# hall_effect_breakout_2025-11-21.net
KiCad netlist of a schematic drawn in EasyEDA Pro
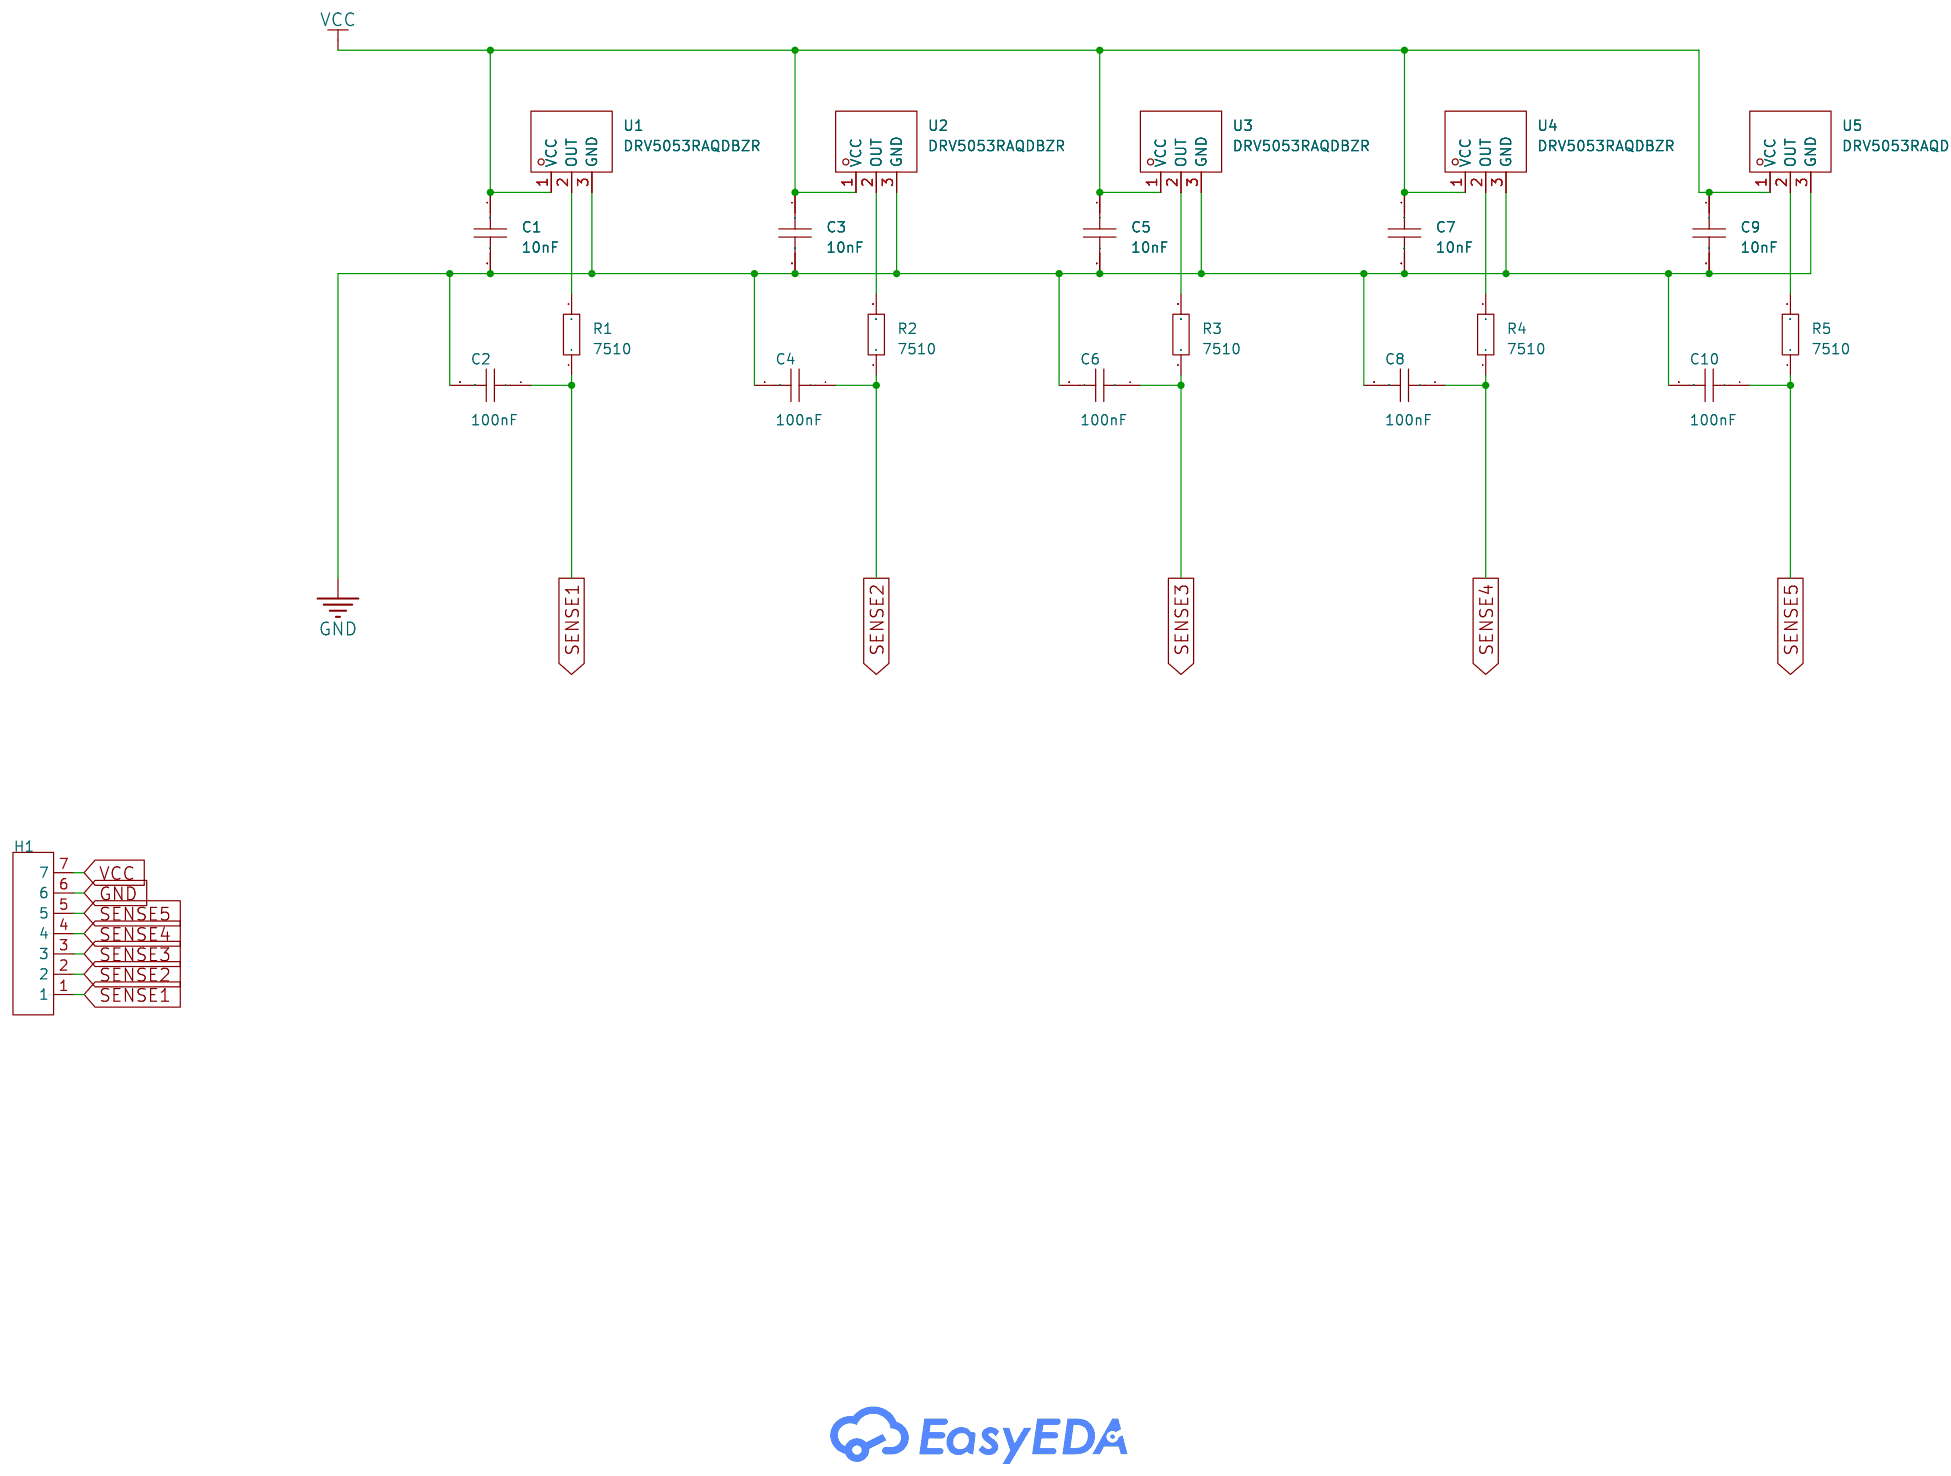
[diagram p0: schematic sheet]

(export (version "E")
  (design (tool "Eeschema 10.0.6"))
  (components
    (comp (ref "C1")
      (value "10nF")
      (footprint "easyedapro:C0603")
      (libsource (lib "easyedapro") (part "CAP"))
    )
    (comp (ref "C2")
      (value "100nF")
      (footprint "easyedapro:C0603")
      (libsource (lib "easyedapro") (part "CAP"))
    )
    (comp (ref "C3")
      (value "10nF")
      (footprint "easyedapro:C0603")
      (libsource (lib "easyedapro") (part "CAP"))
    )
    (comp (ref "C4")
      (value "100nF")
      (footprint "easyedapro:C0603")
      (libsource (lib "easyedapro") (part "CAP"))
    )
    (comp (ref "C5")
      (value "10nF")
      (footprint "easyedapro:C0603")
      (libsource (lib "easyedapro") (part "CAP"))
    )
    (comp (ref "C6")
      (value "100nF")
      (footprint "easyedapro:C0603")
      (libsource (lib "easyedapro") (part "CAP"))
    )
    (comp (ref "C7")
      (value "10nF")
      (footprint "easyedapro:C0603")
      (libsource (lib "easyedapro") (part "CAP"))
    )
    (comp (ref "C8")
      (value "100nF")
      (footprint "easyedapro:C0603")
      (libsource (lib "easyedapro") (part "CAP"))
    )
    (comp (ref "C9")
      (value "10nF")
      (footprint "easyedapro:C0603")
      (libsource (lib "easyedapro") (part "CAP"))
    )
    (comp (ref "C10")
      (value "100nF")
      (footprint "easyedapro:C0603")
      (libsource (lib "easyedapro") (part "CAP"))
    )
    (comp (ref "H1")
      (value "PZ254V-11-07P")
      (footprint "easyedapro:HDR-TH_7P-P2.54-V-M")
      (fields (field (name "Manufacturer") "XFCN(兴飞)"))
      (libsource (lib "easyedapro") (part "PZ254V-11-07P"))
    )
    (comp (ref "R1")
      (value "7510")
      (footprint "easyedapro:R0603")
      (libsource (lib "easyedapro") (part "Res"))
    )
    (comp (ref "R2")
      (value "7510")
      (footprint "easyedapro:R0603")
      (libsource (lib "easyedapro") (part "Res"))
    )
    (comp (ref "R3")
      (value "7510")
      (footprint "easyedapro:R0603")
      (libsource (lib "easyedapro") (part "Res"))
    )
    (comp (ref "R4")
      (value "7510")
      (footprint "easyedapro:R0603")
      (libsource (lib "easyedapro") (part "Res"))
    )
    (comp (ref "R5")
      (value "7510")
      (footprint "easyedapro:R0603")
      (libsource (lib "easyedapro") (part "Res"))
    )
    (comp (ref "U1")
      (value "DRV5053RAQDBZR")
      (footprint "easyedapro:SOT-23-3_L2.9-W1.3-P1.90-LS2.4-BR")
      (fields (field (name "Manufacturer") "TI(德州仪器)"))
      (libsource (lib "easyedapro") (part "DRV5053EAQDBZTQ1"))
    )
    (comp (ref "U2")
      (value "DRV5053RAQDBZR")
      (footprint "easyedapro:SOT-23-3_L2.9-W1.3-P1.90-LS2.4-BR")
      (fields (field (name "Manufacturer") "TI(德州仪器)"))
      (libsource (lib "easyedapro") (part "DRV5053EAQDBZTQ1"))
    )
    (comp (ref "U3")
      (value "DRV5053RAQDBZR")
      (footprint "easyedapro:SOT-23-3_L2.9-W1.3-P1.90-LS2.4-BR")
      (fields (field (name "Manufacturer") "TI(德州仪器)"))
      (libsource (lib "easyedapro") (part "DRV5053EAQDBZTQ1"))
    )
    (comp (ref "U4")
      (value "DRV5053RAQDBZR")
      (footprint "easyedapro:SOT-23-3_L2.9-W1.3-P1.90-LS2.4-BR")
      (fields (field (name "Manufacturer") "TI(德州仪器)"))
      (libsource (lib "easyedapro") (part "DRV5053EAQDBZTQ1"))
    )
    (comp (ref "U5")
      (value "DRV5053RAQDBZR")
      (footprint "easyedapro:SOT-23-3_L2.9-W1.3-P1.90-LS2.4-BR")
      (fields (field (name "Manufacturer") "TI(德州仪器)"))
      (libsource (lib "easyedapro") (part "DRV5053EAQDBZTQ1"))
    )
  )
  (nets
    (net (code "1") (name "GND") (class "Default")
      (node (ref "C1") (pin "2") (pinfunction "2_2") (pintype "input"))
      (node (ref "C10") (pin "2") (pinfunction "2_2") (pintype "input"))
      (node (ref "C2") (pin "2") (pinfunction "2_2") (pintype "input"))
      (node (ref "C3") (pin "2") (pinfunction "2_2") (pintype "input"))
      (node (ref "C4") (pin "2") (pinfunction "2_2") (pintype "input"))
      (node (ref "C5") (pin "2") (pinfunction "2_2") (pintype "input"))
      (node (ref "C6") (pin "2") (pinfunction "2_2") (pintype "input"))
      (node (ref "C7") (pin "2") (pinfunction "2_2") (pintype "input"))
      (node (ref "C8") (pin "2") (pinfunction "2_2") (pintype "input"))
      (node (ref "C9") (pin "2") (pinfunction "2_2") (pintype "input"))
      (node (ref "H1") (pin "6") (pinfunction "6_6") (pintype "unspecified"))
      (node (ref "U1") (pin "3") (pinfunction "GND_3") (pintype "unspecified"))
      (node (ref "U2") (pin "3") (pinfunction "GND_3") (pintype "unspecified"))
      (node (ref "U3") (pin "3") (pinfunction "GND_3") (pintype "unspecified"))
      (node (ref "U4") (pin "3") (pinfunction "GND_3") (pintype "unspecified"))
      (node (ref "U5") (pin "3") (pinfunction "GND_3") (pintype "unspecified"))
    )
    (net (code "2") (name "Net-(U1-OUT)") (class "Default")
      (node (ref "R1") (pin "2") (pinfunction "2_2") (pintype "input"))
      (node (ref "U1") (pin "2") (pinfunction "OUT_2") (pintype "unspecified"))
    )
    (net (code "3") (name "Net-(U2-OUT)") (class "Default")
      (node (ref "R2") (pin "2") (pinfunction "2_2") (pintype "input"))
      (node (ref "U2") (pin "2") (pinfunction "OUT_2") (pintype "unspecified"))
    )
    (net (code "4") (name "Net-(U3-OUT)") (class "Default")
      (node (ref "R3") (pin "2") (pinfunction "2_2") (pintype "input"))
      (node (ref "U3") (pin "2") (pinfunction "OUT_2") (pintype "unspecified"))
    )
    (net (code "5") (name "Net-(U4-OUT)") (class "Default")
      (node (ref "R4") (pin "2") (pinfunction "2_2") (pintype "input"))
      (node (ref "U4") (pin "2") (pinfunction "OUT_2") (pintype "unspecified"))
    )
    (net (code "6") (name "Net-(U5-OUT)") (class "Default")
      (node (ref "R5") (pin "2") (pinfunction "2_2") (pintype "input"))
      (node (ref "U5") (pin "2") (pinfunction "OUT_2") (pintype "unspecified"))
    )
    (net (code "7") (name "SENSE1") (class "Default")
      (node (ref "C2") (pin "1") (pinfunction "1_1") (pintype "input"))
      (node (ref "H1") (pin "1") (pinfunction "1_1") (pintype "unspecified"))
      (node (ref "R1") (pin "1") (pinfunction "1_1") (pintype "input"))
    )
    (net (code "8") (name "SENSE2") (class "Default")
      (node (ref "C4") (pin "1") (pinfunction "1_1") (pintype "input"))
      (node (ref "H1") (pin "2") (pinfunction "2_2") (pintype "unspecified"))
      (node (ref "R2") (pin "1") (pinfunction "1_1") (pintype "input"))
    )
    (net (code "9") (name "SENSE3") (class "Default")
      (node (ref "C6") (pin "1") (pinfunction "1_1") (pintype "input"))
      (node (ref "H1") (pin "3") (pinfunction "3_3") (pintype "unspecified"))
      (node (ref "R3") (pin "1") (pinfunction "1_1") (pintype "input"))
    )
    (net (code "10") (name "SENSE4") (class "Default")
      (node (ref "C8") (pin "1") (pinfunction "1_1") (pintype "input"))
      (node (ref "H1") (pin "4") (pinfunction "4_4") (pintype "unspecified"))
      (node (ref "R4") (pin "1") (pinfunction "1_1") (pintype "input"))
    )
    (net (code "11") (name "SENSE5") (class "Default")
      (node (ref "C10") (pin "1") (pinfunction "1_1") (pintype "input"))
      (node (ref "H1") (pin "5") (pinfunction "5_5") (pintype "unspecified"))
      (node (ref "R5") (pin "1") (pinfunction "1_1") (pintype "input"))
    )
    (net (code "12") (name "VCC") (class "Default")
      (node (ref "C1") (pin "1") (pinfunction "1_1") (pintype "input"))
      (node (ref "C3") (pin "1") (pinfunction "1_1") (pintype "input"))
      (node (ref "C5") (pin "1") (pinfunction "1_1") (pintype "input"))
      (node (ref "C7") (pin "1") (pinfunction "1_1") (pintype "input"))
      (node (ref "C9") (pin "1") (pinfunction "1_1") (pintype "input"))
      (node (ref "H1") (pin "7") (pinfunction "7_7") (pintype "unspecified"))
      (node (ref "U1") (pin "1") (pinfunction "VCC_1") (pintype "unspecified"))
      (node (ref "U2") (pin "1") (pinfunction "VCC_1") (pintype "unspecified"))
      (node (ref "U3") (pin "1") (pinfunction "VCC_1") (pintype "unspecified"))
      (node (ref "U4") (pin "1") (pinfunction "VCC_1") (pintype "unspecified"))
      (node (ref "U5") (pin "1") (pinfunction "VCC_1") (pintype "unspecified"))
    )
  )
)
